# regulators.net
KiCad netlist of a schematic drawn in Altium Designer
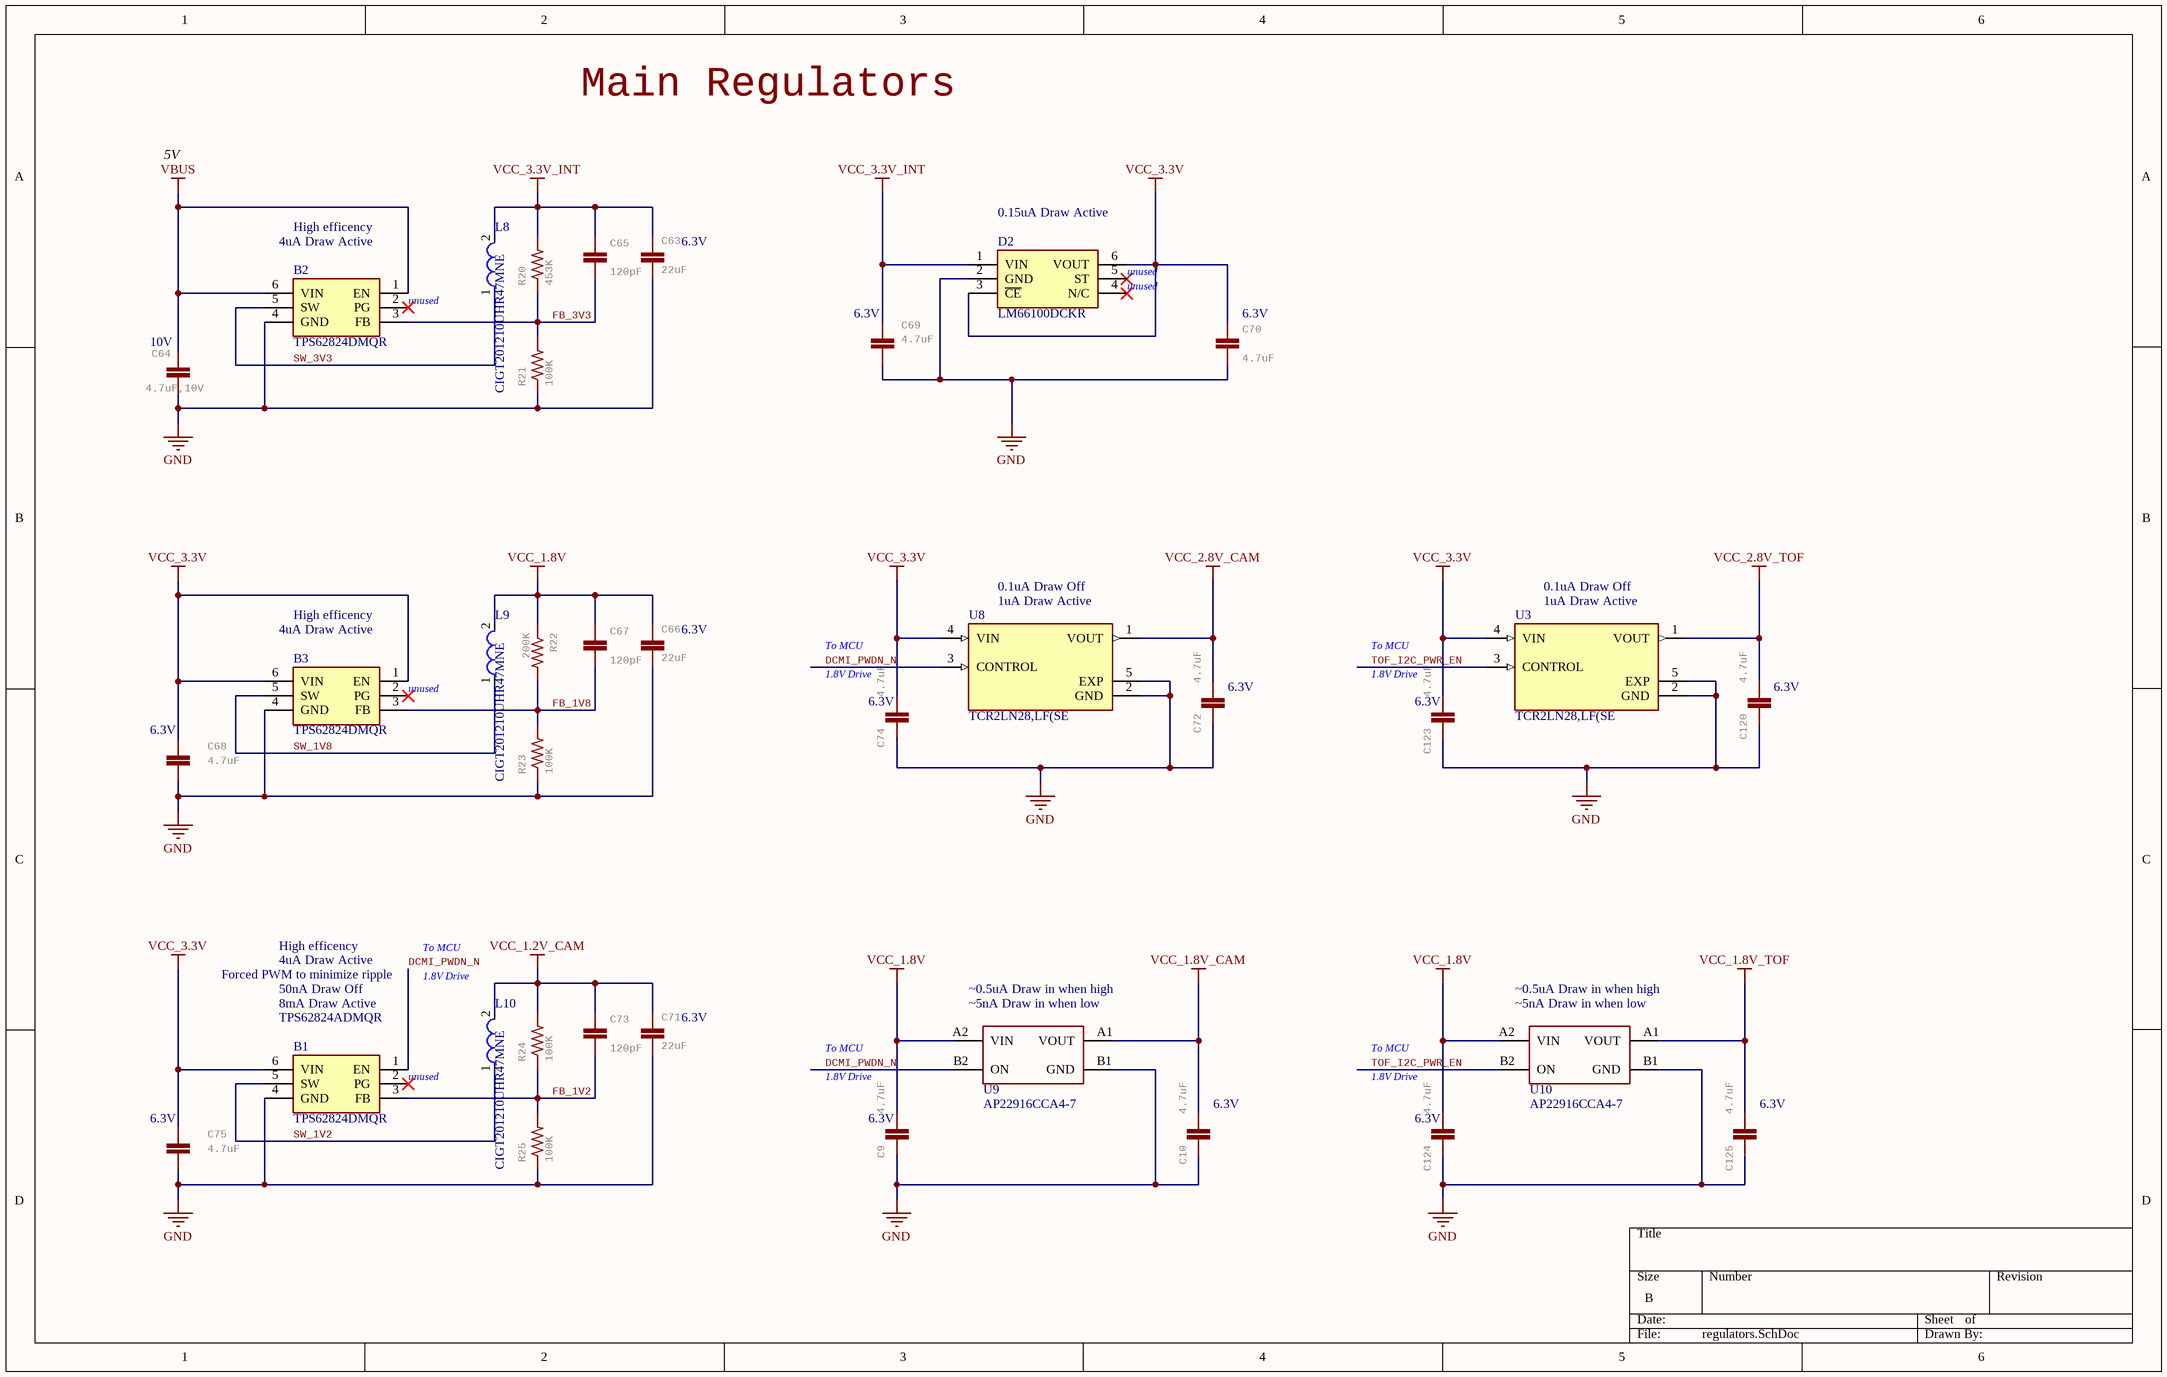
[diagram p0: regulators.SchDoc]

(export (version "E")
  (design (tool "Eeschema 10.0.6"))
  (components
    (comp (ref "B1")
      (value "TPS62824DMQR")
      (footprint "TPS62826ADMQR")
      (fields (field (name "MOUSER PART NUMBER") "595-TPS62824DMQR"))
      (libsource (lib "openmv-ae3") (part "TPS62826ADMQR"))
    )
    (comp (ref "B2")
      (value "TPS62824DMQR")
      (footprint "TPS62826ADMQR")
      (fields
        (field (name "MOUSER PART NUMBER") "595-TPS62826DMQR")
        (field (name "MANUFACTURER_PART_NUMBER") "TPS62826DMQR")
      )
      (libsource (lib "openmv-ae3") (part "TPS62826ADMQR"))
    )
    (comp (ref "B3")
      (value "TPS62824DMQR")
      (footprint "TPS62826ADMQR")
      (fields (field (name "MOUSER PART NUMBER") "595-TPS62824DMQR"))
      (libsource (lib "openmv-ae3") (part "TPS62826ADMQR"))
    )
    (comp (ref "C9")
      (value "4.7uF")
      (footprint "0402-CAP")
      (description "0402 (1005 Metric) Nick Garner - TeleSense")
      (fields (field (name "MPN") "JMK105BBJ475MV-F"))
      (libsource (lib "openmv-ae3") (part "CAP_0402"))
    )
    (comp (ref "C10")
      (value "4.7uF")
      (footprint "0402-CAP")
      (description "0402 (1005 Metric) Nick Garner - TeleSense")
      (fields (field (name "MPN") "JMK105BBJ475MV-F"))
      (libsource (lib "openmv-ae3") (part "CAP_0402"))
    )
    (comp (ref "C63")
      (value "22uF")
      (footprint "0805")
      (fields (field (name "MPN") "CL21A226MQQNNNE"))
      (libsource (lib "openmv-ae3") (part "22UF-0805-6.3V-20%"))
    )
    (comp (ref "C64")
      (value "4.7uF,10V")
      (footprint "0402-CAP")
      (description "CapacitorStandard 0603 ceramic capacitor, and 0.1\" leaded capacitor.")
      (fields (field (name "MPN") "CL05A475MP5NRNC") (field (name "LIBRARYNAME") "sfe"))
      (libsource (lib "openmv-ae3") (part "CAP0402-CAP"))
    )
    (comp (ref "C65")
      (value "120pF")
      (footprint "C0201")
      (fields (field (name "MPN") "GRM033R71H121KA12D") (field (name "LIBRARYNAME") "sfe"))
      (libsource (lib "") (part "CAP0402-CAP_1"))
    )
    (comp (ref "C66")
      (value "22uF")
      (footprint "0805")
      (fields (field (name "MPN") "CL21A226MQQNNNE"))
      (libsource (lib "openmv-ae3") (part "22UF-0805-6.3V-20%"))
    )
    (comp (ref "C67")
      (value "120pF")
      (footprint "C0201")
      (fields (field (name "MPN") "GRM033R71H121KA12D") (field (name "LIBRARYNAME") "sfe"))
      (libsource (lib "") (part "CAP0402-CAP_1"))
    )
    (comp (ref "C68")
      (value "4.7uF")
      (footprint "0402-CAP")
      (description "CapacitorStandard 0603 ceramic capacitor, and 0.1\" leaded capacitor.")
      (fields (field (name "MPN") "JMK105BBJ475MV-F") (field (name "LIBRARYNAME") "sfe"))
      (libsource (lib "") (part "CAP0402-CAP_1"))
    )
    (comp (ref "C69")
      (value "4.7uF")
      (footprint "0402-CAP")
      (description "CapacitorStandard 0603 ceramic capacitor, and 0.1\" leaded capacitor.")
      (fields (field (name "MPN") "JMK105BBJ475MV-F") (field (name "LIBRARYNAME") "sfe"))
      (libsource (lib "") (part "CAP0402-CAP_1"))
    )
    (comp (ref "C70")
      (value "4.7uF")
      (footprint "0402-CAP")
      (description "CapacitorStandard 0603 ceramic capacitor, and 0.1\" leaded capacitor.")
      (fields (field (name "MPN") "JMK105BBJ475MV-F") (field (name "LIBRARYNAME") "sfe"))
      (libsource (lib "") (part "CAP0402-CAP_1"))
    )
    (comp (ref "C71")
      (value "22uF")
      (footprint "0805")
      (fields (field (name "MPN") "CL21A226MQQNNNE"))
      (libsource (lib "openmv-ae3") (part "22UF-0805-6.3V-20%"))
    )
    (comp (ref "C72")
      (value "4.7uF")
      (footprint "0402-CAP")
      (description "0402 (1005 Metric) Nick Garner - TeleSense")
      (fields (field (name "MPN") "JMK105BBJ475MV-F"))
      (libsource (lib "openmv-ae3") (part "CAP_0402"))
    )
    (comp (ref "C73")
      (value "120pF")
      (footprint "C0201")
      (fields (field (name "MPN") "GRM033R71H121KA12D") (field (name "LIBRARYNAME") "sfe"))
      (libsource (lib "") (part "CAP0402-CAP_1"))
    )
    (comp (ref "C74")
      (value "4.7uF")
      (footprint "0402-CAP")
      (description "0402 (1005 Metric) Nick Garner - TeleSense")
      (fields (field (name "MPN") "JMK105BBJ475MV-F"))
      (libsource (lib "openmv-ae3") (part "CAP_0402"))
    )
    (comp (ref "C75")
      (value "4.7uF")
      (footprint "0402-CAP")
      (description "CapacitorStandard 0603 ceramic capacitor, and 0.1\" leaded capacitor.")
      (fields (field (name "MPN") "JMK105BBJ475MV-F") (field (name "LIBRARYNAME") "sfe"))
      (libsource (lib "") (part "CAP0402-CAP_1"))
    )
    (comp (ref "C120")
      (value "4.7uF")
      (footprint "0402-CAP")
      (description "0402 (1005 Metric) Nick Garner - TeleSense")
      (fields (field (name "MPN") "JMK105BBJ475MV-F"))
      (libsource (lib "openmv-ae3") (part "CAP_0402"))
    )
    (comp (ref "C123")
      (value "4.7uF")
      (footprint "0402-CAP")
      (description "0402 (1005 Metric) Nick Garner - TeleSense")
      (fields (field (name "MPN") "JMK105BBJ475MV-F"))
      (libsource (lib "openmv-ae3") (part "CAP_0402"))
    )
    (comp (ref "C124")
      (value "4.7uF")
      (footprint "0402-CAP")
      (description "0402 (1005 Metric) Nick Garner - TeleSense")
      (fields (field (name "MPN") "JMK105BBJ475MV-F"))
      (libsource (lib "openmv-ae3") (part "CAP_0402"))
    )
    (comp (ref "C125")
      (value "4.7uF")
      (footprint "0402-CAP")
      (description "0402 (1005 Metric) Nick Garner - TeleSense")
      (fields (field (name "MPN") "JMK105BBJ475MV-F"))
      (libsource (lib "openmv-ae3") (part "CAP_0402"))
    )
    (comp (ref "D2")
      (value "LM66100DCKR")
      (footprint "SamacSys:SOP65P210X110-6N")
      (description "Diode")
      (fields
        (field (name "MANUFACTURER_PART_NUMBER") "c")
        (field (name "MOUSER PART NUMBER") "595-LM66100DCKR")
      )
      (libsource (lib "openmv-ae3") (part "LM66100DCKR"))
    )
    (comp (ref "L8")
      (value "CIGT201210UHR47MNE")
      (footprint "0805")
      (description "Power Inductor : LxW size(mm) 2012 Thickness1 Inductance (uH) 20%: 0.47")
      (fields (field (name "TOLERANCE") "20%"))
      (libsource (lib "openmv-ae3") (part "CMP-00002-1"))
    )
    (comp (ref "L9")
      (value "CIGT201210UHR47MNE")
      (footprint "0805")
      (description "Power Inductor : LxW size(mm) 2012 Thickness1 Inductance (uH) 20%: 0.47")
      (fields (field (name "TOLERANCE") "20%"))
      (libsource (lib "openmv-ae3") (part "CMP-00002-1"))
    )
    (comp (ref "L10")
      (value "CIGT201210UHR47MNE")
      (footprint "0805")
      (description "Power Inductor : LxW size(mm) 2012 Thickness1 Inductance (uH) 20%: 0.47")
      (fields (field (name "TOLERANCE") "20%"))
      (libsource (lib "openmv-ae3") (part "CMP-00002-1"))
    )
    (comp (ref "R20")
      (value "453K")
      (footprint "R0201")
      (fields (field (name "MPN") "ERJ-1GNF4533C") (field (name "LIBRARYNAME") "sfe"))
      (libsource (lib "openmv-ae3") (part "RESISTOR0402-RES"))
    )
    (comp (ref "R21")
      (value "100K")
      (footprint "R0201")
      (fields (field (name "MPN") "RMCF0201FT100K") (field (name "LIBRARYNAME") "sfe"))
      (libsource (lib "openmv-ae3") (part "RESISTOR0402-RES"))
    )
    (comp (ref "R22")
      (value "200K")
      (footprint "R0201")
      (fields (field (name "MPN") "RC0201JR-07200KL") (field (name "LIBRARYNAME") "sfe"))
      (libsource (lib "openmv-ae3") (part "RESISTOR0402-RES"))
    )
    (comp (ref "R23")
      (value "100K")
      (footprint "R0201")
      (fields (field (name "MPN") "RMCF0201FT100K") (field (name "LIBRARYNAME") "sfe"))
      (libsource (lib "openmv-ae3") (part "RESISTOR0402-RES"))
    )
    (comp (ref "R24")
      (value "100K")
      (footprint "R0201")
      (fields (field (name "MPN") "RMCF0201FT100K") (field (name "LIBRARYNAME") "sfe"))
      (libsource (lib "openmv-ae3") (part "RESISTOR0402-RES"))
    )
    (comp (ref "R25")
      (value "100K")
      (footprint "R0201")
      (fields (field (name "MPN") "RMCF0201FT100K") (field (name "LIBRARYNAME") "sfe"))
      (libsource (lib "openmv-ae3") (part "RESISTOR0402-RES"))
    )
    (comp (ref "U3")
      (value "TCR2LN28,LF(SE")
      (footprint "VREG_TCR2LN30_LF")
      (description "Linear Voltage Regulator IC Positive Fixed 1 Output 200mA 4-SDFN (0.8x0.8)")
      (fields (field (name "MF") "Toshiba Semiconductor"))
      (libsource (lib "openmv-ae3") (part "TCR2LN30_LF"))
    )
    (comp (ref "U8")
      (value "TCR2LN28,LF(SE")
      (footprint "VREG_TCR2LN30_LF")
      (description "Linear Voltage Regulator IC Positive Fixed 1 Output 200mA 4-SDFN (0.8x0.8)")
      (fields (field (name "MF") "Toshiba Semiconductor"))
      (libsource (lib "openmv-ae3") (part "TCR2LN30_LF"))
    )
    (comp (ref "U9")
      (value "PMOS Load Switch")
      (footprint "AP22916CCA4-7")
      (fields
        (field (name "MPN") "AP22916CCA4-7")
        (field (name "MF") "Diodes Inc")
        (field (name "PART NUMBER") "AP22916CCA4-7")
      )
      (libsource (lib "openmv-ae3") (part "AP22916CCA4-7"))
    )
    (comp (ref "U10")
      (value "PMOS Load Switch")
      (footprint "AP22916CCA4-7")
      (fields
        (field (name "MPN") "AP22916CCA4-7")
        (field (name "MF") "Diodes Inc")
        (field (name "PART NUMBER") "AP22916CCA4-7")
      )
      (libsource (lib "openmv-ae3") (part "AP22916CCA4-7"))
    )
  )
  (nets
    (net (code "1") (name "/DCMI_PWDN_N") (class "Default")
      (node (ref "B1") (pin "1") (pinfunction "EN_1") (pintype "passive"))
      (node (ref "U8") (pin "3") (pinfunction "CONTROL_3") (pintype "input"))
      (node (ref "U9") (pin "B2") (pinfunction "ON_B2") (pintype "passive"))
    )
    (net (code "2") (name "/FB_1V2") (class "Default")
      (node (ref "B1") (pin "3") (pinfunction "FB_3") (pintype "passive"))
      (node (ref "C73") (pin "1") (pinfunction "1_1") (pintype "passive"))
      (node (ref "R24") (pin "1") (pinfunction "1_1") (pintype "passive"))
      (node (ref "R25") (pin "2") (pinfunction "2_2") (pintype "passive"))
    )
    (net (code "3") (name "/FB_1V8") (class "Default")
      (node (ref "B3") (pin "3") (pinfunction "FB_3") (pintype "passive"))
      (node (ref "C67") (pin "1") (pinfunction "1_1") (pintype "passive"))
      (node (ref "R22") (pin "2") (pinfunction "2_2") (pintype "passive"))
      (node (ref "R23") (pin "2") (pinfunction "2_2") (pintype "passive"))
    )
    (net (code "4") (name "/FB_3V3") (class "Default")
      (node (ref "B2") (pin "3") (pinfunction "FB_3") (pintype "passive"))
      (node (ref "C65") (pin "1") (pinfunction "1_1") (pintype "passive"))
      (node (ref "R20") (pin "1") (pinfunction "1_1") (pintype "passive"))
      (node (ref "R21") (pin "2") (pinfunction "2_2") (pintype "passive"))
    )
    (net (code "5") (name "/SW_1V2") (class "Default")
      (node (ref "B1") (pin "5") (pinfunction "SW_5") (pintype "passive"))
      (node (ref "L10") (pin "1") (pinfunction "1_1") (pintype "passive"))
    )
    (net (code "6") (name "/SW_1V8") (class "Default")
      (node (ref "B3") (pin "5") (pinfunction "SW_5") (pintype "passive"))
      (node (ref "L9") (pin "1") (pinfunction "1_1") (pintype "passive"))
    )
    (net (code "7") (name "/SW_3V3") (class "Default")
      (node (ref "B2") (pin "5") (pinfunction "SW_5") (pintype "passive"))
      (node (ref "L8") (pin "1") (pinfunction "1_1") (pintype "passive"))
    )
    (net (code "8") (name "/TOF_I2C_PWR_EN") (class "Default")
      (node (ref "U10") (pin "B2") (pinfunction "ON_B2") (pintype "passive"))
      (node (ref "U3") (pin "3") (pinfunction "CONTROL_3") (pintype "input"))
    )
    (net (code "9") (name "GND") (class "Default")
      (node (ref "B1") (pin "4") (pinfunction "GND_4") (pintype "passive"))
      (node (ref "B2") (pin "4") (pinfunction "GND_4") (pintype "passive"))
      (node (ref "B3") (pin "4") (pinfunction "GND_4") (pintype "passive"))
      (node (ref "C10") (pin "1") (pinfunction "1_1") (pintype "passive"))
      (node (ref "C120") (pin "1") (pinfunction "1_1") (pintype "passive"))
      (node (ref "C123") (pin "1") (pinfunction "1_1") (pintype "passive"))
      (node (ref "C124") (pin "1") (pinfunction "1_1") (pintype "passive"))
      (node (ref "C125") (pin "1") (pinfunction "1_1") (pintype "passive"))
      (node (ref "C63") (pin "2") (pinfunction "2_2") (pintype "passive"))
      (node (ref "C64") (pin "2") (pinfunction "2_2") (pintype "passive"))
      (node (ref "C66") (pin "2") (pinfunction "2_2") (pintype "passive"))
      (node (ref "C68") (pin "1") (pinfunction "1_1") (pintype "passive"))
      (node (ref "C69") (pin "1") (pinfunction "1_1") (pintype "passive"))
      (node (ref "C70") (pin "1") (pinfunction "1_1") (pintype "passive"))
      (node (ref "C71") (pin "2") (pinfunction "2_2") (pintype "passive"))
      (node (ref "C72") (pin "1") (pinfunction "1_1") (pintype "passive"))
      (node (ref "C74") (pin "1") (pinfunction "1_1") (pintype "passive"))
      (node (ref "C75") (pin "1") (pinfunction "1_1") (pintype "passive"))
      (node (ref "C9") (pin "1") (pinfunction "1_1") (pintype "passive"))
      (node (ref "D2") (pin "2") (pinfunction "GND_2") (pintype "passive"))
      (node (ref "R21") (pin "1") (pinfunction "1_1") (pintype "passive"))
      (node (ref "R23") (pin "1") (pinfunction "1_1") (pintype "passive"))
      (node (ref "R25") (pin "1") (pinfunction "1_1") (pintype "passive"))
      (node (ref "U10") (pin "B1") (pinfunction "GND_B1") (pintype "passive"))
      (node (ref "U3") (pin "2") (pinfunction "GND_2") (pintype "power_in"))
      (node (ref "U3") (pin "5") (pinfunction "EXP_5") (pintype "power_in"))
      (node (ref "U8") (pin "2") (pinfunction "GND_2") (pintype "power_in"))
      (node (ref "U8") (pin "5") (pinfunction "EXP_5") (pintype "power_in"))
      (node (ref "U9") (pin "B1") (pinfunction "GND_B1") (pintype "passive"))
    )
    (net (code "10") (name "VBUS") (class "Default")
      (node (ref "B2") (pin "1") (pinfunction "EN_1") (pintype "passive"))
      (node (ref "B2") (pin "6") (pinfunction "VIN_6") (pintype "passive"))
      (node (ref "C64") (pin "1") (pinfunction "1_1") (pintype "passive"))
    )
    (net (code "11") (name "VCC_1.2V_CAM") (class "Default")
      (node (ref "C71") (pin "1") (pinfunction "1_1") (pintype "passive"))
      (node (ref "C73") (pin "2") (pinfunction "2_2") (pintype "passive"))
      (node (ref "L10") (pin "2") (pinfunction "2_2") (pintype "passive"))
      (node (ref "R24") (pin "2") (pinfunction "2_2") (pintype "passive"))
    )
    (net (code "12") (name "VCC_1.8V") (class "Default")
      (node (ref "C124") (pin "2") (pinfunction "2_2") (pintype "passive"))
      (node (ref "C66") (pin "1") (pinfunction "1_1") (pintype "passive"))
      (node (ref "C67") (pin "2") (pinfunction "2_2") (pintype "passive"))
      (node (ref "C9") (pin "2") (pinfunction "2_2") (pintype "passive"))
      (node (ref "L9") (pin "2") (pinfunction "2_2") (pintype "passive"))
      (node (ref "R22") (pin "1") (pinfunction "1_1") (pintype "passive"))
      (node (ref "U10") (pin "A2") (pinfunction "VIN_A2") (pintype "passive"))
      (node (ref "U9") (pin "A2") (pinfunction "VIN_A2") (pintype "passive"))
    )
    (net (code "13") (name "VCC_1.8V_CAM") (class "Default")
      (node (ref "C10") (pin "2") (pinfunction "2_2") (pintype "passive"))
      (node (ref "U9") (pin "A1") (pinfunction "VOUT_A1") (pintype "passive"))
    )
    (net (code "14") (name "VCC_1.8V_TOF") (class "Default")
      (node (ref "C125") (pin "2") (pinfunction "2_2") (pintype "passive"))
      (node (ref "U10") (pin "A1") (pinfunction "VOUT_A1") (pintype "passive"))
    )
    (net (code "15") (name "VCC_2.8V_CAM") (class "Default")
      (node (ref "C72") (pin "2") (pinfunction "2_2") (pintype "passive"))
      (node (ref "U8") (pin "1") (pinfunction "VOUT_1") (pintype "output"))
    )
    (net (code "16") (name "VCC_2.8V_TOF") (class "Default")
      (node (ref "C120") (pin "2") (pinfunction "2_2") (pintype "passive"))
      (node (ref "U3") (pin "1") (pinfunction "VOUT_1") (pintype "output"))
    )
    (net (code "17") (name "VCC_3.3V") (class "Default")
      (node (ref "B1") (pin "6") (pinfunction "VIN_6") (pintype "passive"))
      (node (ref "B3") (pin "1") (pinfunction "EN_1") (pintype "passive"))
      (node (ref "B3") (pin "6") (pinfunction "VIN_6") (pintype "passive"))
      (node (ref "C123") (pin "2") (pinfunction "2_2") (pintype "passive"))
      (node (ref "C68") (pin "2") (pinfunction "2_2") (pintype "passive"))
      (node (ref "C70") (pin "2") (pinfunction "2_2") (pintype "passive"))
      (node (ref "C74") (pin "2") (pinfunction "2_2") (pintype "passive"))
      (node (ref "C75") (pin "2") (pinfunction "2_2") (pintype "passive"))
      (node (ref "D2") (pin "3") (pinfunction "~{CE}_3") (pintype "passive"))
      (node (ref "D2") (pin "6") (pinfunction "VOUT_6") (pintype "passive"))
      (node (ref "U3") (pin "4") (pinfunction "VIN_4") (pintype "input"))
      (node (ref "U8") (pin "4") (pinfunction "VIN_4") (pintype "input"))
    )
    (net (code "18") (name "VCC_3.3V_INT") (class "Default")
      (node (ref "C63") (pin "1") (pinfunction "1_1") (pintype "passive"))
      (node (ref "C65") (pin "2") (pinfunction "2_2") (pintype "passive"))
      (node (ref "C69") (pin "2") (pinfunction "2_2") (pintype "passive"))
      (node (ref "D2") (pin "1") (pinfunction "VIN_1") (pintype "passive"))
      (node (ref "L8") (pin "2") (pinfunction "2_2") (pintype "passive"))
      (node (ref "R20") (pin "2") (pinfunction "2_2") (pintype "passive"))
    )
    (net (code "19") (name "unconnected-(B1-PG-Pad2)") (class "Default")
      (node (ref "B1") (pin "2") (pinfunction "PG_2") (pintype "passive+no_connect"))
    )
    (net (code "20") (name "unconnected-(B2-PG-Pad2)") (class "Default")
      (node (ref "B2") (pin "2") (pinfunction "PG_2") (pintype "passive+no_connect"))
    )
    (net (code "21") (name "unconnected-(B3-PG-Pad2)") (class "Default")
      (node (ref "B3") (pin "2") (pinfunction "PG_2") (pintype "passive+no_connect"))
    )
    (net (code "22") (name "unconnected-(D2-N{slash}C-Pad4)") (class "Default")
      (node (ref "D2") (pin "4") (pinfunction "N/C_4") (pintype "passive+no_connect"))
    )
    (net (code "23") (name "unconnected-(D2-ST-Pad5)") (class "Default")
      (node (ref "D2") (pin "5") (pinfunction "ST_5") (pintype "passive+no_connect"))
    )
  )
)
